# Driver.net
KiCad netlist of a schematic drawn in Altium Designer
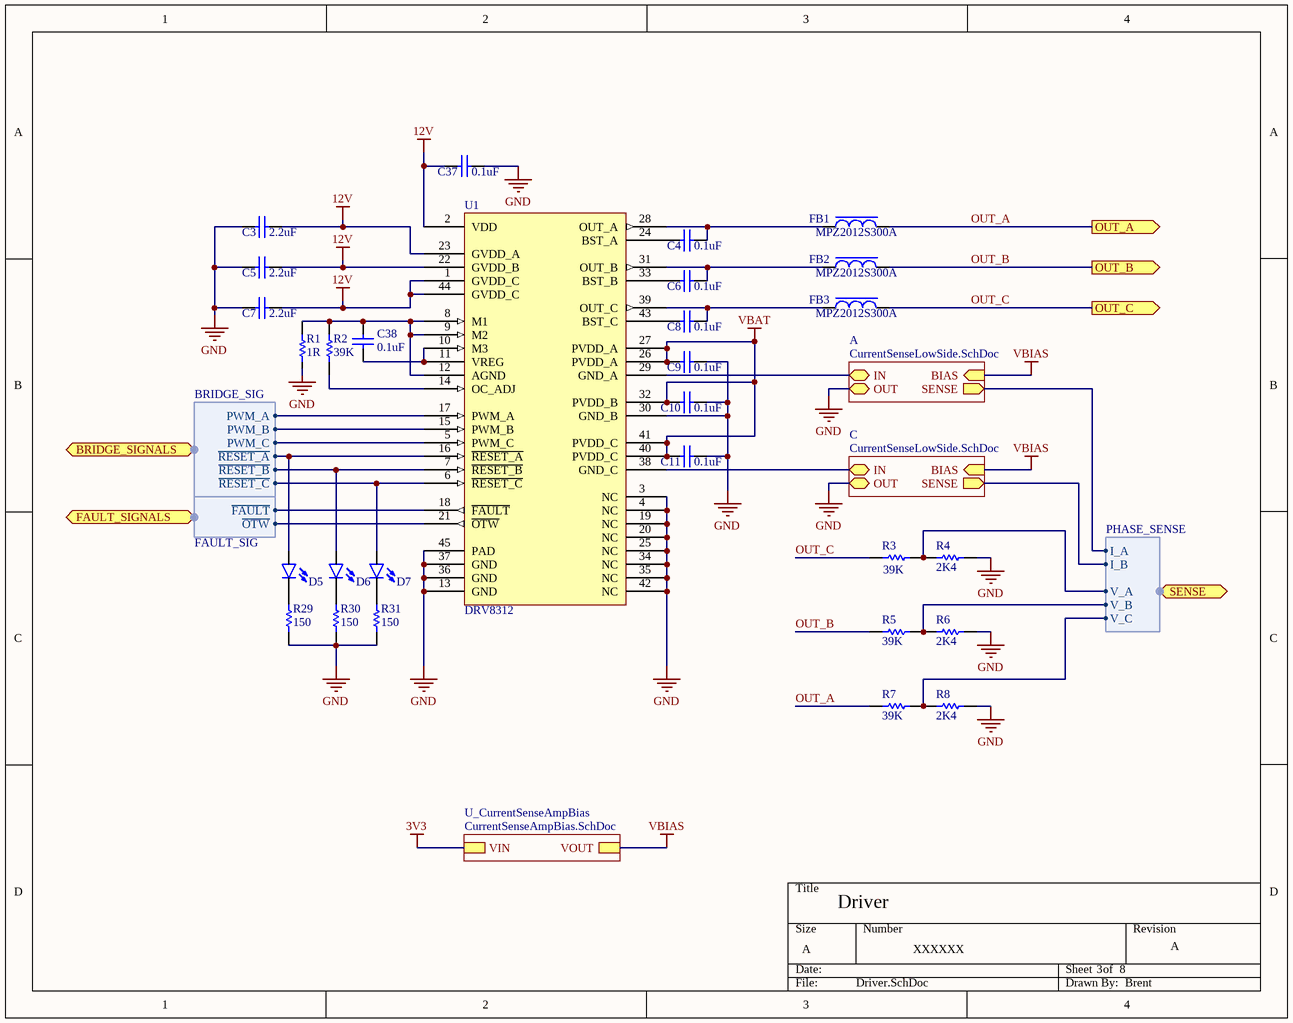
[diagram p0: Driver.SchDoc]

(export (version "E")
  (design (tool "Eeschema 10.0.6"))
  (components
    (comp (ref "C3")
      (value "2.2uF")
      (footprint "CAPC0603(1608)100_L")
      (description "CAP 2.2uF 25V ±10% 0603 (1608 Metric) Thickness 1mm SMD")
      (fields (field (name "TOLERANCE") "Â±10%"))
      (libsource (lib "Altium Content Vault") (part "CMP-1035-02767-1"))
    )
    (comp (ref "C4")
      (value "0.1uF")
      (footprint "CAPC0603(1608)100_L")
      (description "CAP 100nF 100V ±10% 0603 (1608 Metric) Thickness 1mm SMD")
      (fields (field (name "TOLERANCE") "Â±10%"))
      (libsource (lib "Altium Content Vault") (part "CAP"))
    )
    (comp (ref "C5")
      (value "2.2uF")
      (footprint "CAPC0603(1608)100_L")
      (description "CAP 2.2uF 25V ±10% 0603 (1608 Metric) Thickness 1mm SMD")
      (fields (field (name "TOLERANCE") "Â±10%"))
      (libsource (lib "Altium Content Vault") (part "CMP-1035-02767-1"))
    )
    (comp (ref "C6")
      (value "0.1uF")
      (footprint "CAPC0603(1608)100_L")
      (description "CAP 100nF 100V ±10% 0603 (1608 Metric) Thickness 1mm SMD")
      (fields (field (name "TOLERANCE") "Â±10%"))
      (libsource (lib "Altium Content Vault") (part "CAP"))
    )
    (comp (ref "C7")
      (value "2.2uF")
      (footprint "CAPC0603(1608)100_L")
      (description "CAP 2.2uF 25V ±10% 0603 (1608 Metric) Thickness 1mm SMD")
      (fields (field (name "TOLERANCE") "Â±10%"))
      (libsource (lib "Altium Content Vault") (part "CMP-1035-02767-1"))
    )
    (comp (ref "C8")
      (value "0.1uF")
      (footprint "CAPC0603(1608)100_L")
      (description "CAP 100nF 100V ±10% 0603 (1608 Metric) Thickness 1mm SMD")
      (fields (field (name "TOLERANCE") "Â±10%"))
      (libsource (lib "Altium Content Vault") (part "CAP"))
    )
    (comp (ref "C9")
      (value "0.1uF")
      (footprint "CAPC0603(1608)100_L")
      (description "CAP 100nF 100V ±10% 0603 (1608 Metric) Thickness 1mm SMD")
      (fields (field (name "TOLERANCE") "Â±10%"))
      (libsource (lib "Altium Content Vault") (part "CAP"))
    )
    (comp (ref "C10")
      (value "0.1uF")
      (footprint "CAPC0603(1608)100_L")
      (description "CAP 100nF 100V ±10% 0603 (1608 Metric) Thickness 1mm SMD")
      (fields (field (name "TOLERANCE") "Â±10%"))
      (libsource (lib "Altium Content Vault") (part "CAP"))
    )
    (comp (ref "C11")
      (value "0.1uF")
      (footprint "CAPC0603(1608)100_L")
      (description "CAP 100nF 100V ±10% 0603 (1608 Metric) Thickness 1mm SMD")
      (fields (field (name "TOLERANCE") "Â±10%"))
      (libsource (lib "Altium Content Vault") (part "CAP"))
    )
    (comp (ref "C37")
      (value "0.1uF")
      (footprint "CAPC0603(1608)100_L")
      (description "CAP 100nF 100V ±10% 0603 (1608 Metric) Thickness 1mm SMD")
      (fields (field (name "TOLERANCE") "Â±10%"))
      (libsource (lib "Altium Content Vault") (part "CAP"))
    )
    (comp (ref "C38")
      (value "0.1uF")
      (footprint "CAPC0603(1608)100_L")
      (description "CAP 100nF 100V ±10% 0603 (1608 Metric) Thickness 1mm SMD")
      (fields (field (name "TOLERANCE") "Â±10%"))
      (libsource (lib "Altium Content Vault") (part "CAP"))
    )
    (comp (ref "D5")
      (value "LED_0603_BLUE_5mA")
      (footprint "LED0603")
      (fields (field (name "PARTNUMBER") "LTST-C193TBKT-5A") (field (name "MANUFACTURER") "Lite-On Inc."))
      (libsource (lib "LEDs") (part "LED_0603_BLUE_5mA"))
    )
    (comp (ref "D6")
      (value "LED_0603_BLUE_5mA")
      (footprint "LED0603")
      (fields (field (name "PARTNUMBER") "LTST-C193TBKT-5A") (field (name "MANUFACTURER") "Lite-On Inc."))
      (libsource (lib "LEDs") (part "LED_0603_BLUE_5mA"))
    )
    (comp (ref "D7")
      (value "LED_0603_BLUE_5mA")
      (footprint "LED0603")
      (fields (field (name "PARTNUMBER") "LTST-C193TBKT-5A") (field (name "MANUFACTURER") "Lite-On Inc."))
      (libsource (lib "LEDs") (part "LED_0603_BLUE_5mA"))
    )
    (comp (ref "FB1")
      (value "MPZ2012S300A")
      (footprint "0805-Ferrite")
      (libsource (lib "Components") (part "MPZ2012S300A"))
    )
    (comp (ref "FB2")
      (value "MPZ2012S300A")
      (footprint "0805-Ferrite")
      (libsource (lib "Components") (part "MPZ2012S300A"))
    )
    (comp (ref "FB3")
      (value "MPZ2012S300A")
      (footprint "0805-Ferrite")
      (libsource (lib "Components") (part "MPZ2012S300A"))
    )
    (comp (ref "R1")
      (value "1R")
      (footprint "RESC0603(1608)_L")
      (description "1R 0.1W 5% 0603 (1608 Metric)  SMD")
      (fields (field (name "POWER") "0.1 W") (field (name "TOLERANCE") "5 %"))
      (libsource (lib "Altium Content Vault") (part "CMP-1012-00002-1"))
    )
    (comp (ref "R2")
      (value "39K")
      (footprint "RESC0603(1608)_L")
      (description "39K 0.1W 1% 0603 (1608 Metric)  SMD")
      (fields (field (name "TOLERANCE") "1 %") (field (name "POWER") "0.1 W"))
      (libsource (lib "Altium Content Vault") (part "CMP-1012-00689-1"))
    )
    (comp (ref "R3")
      (value "39K")
      (footprint "RESC0603(1608)_L")
      (description "39K 0.1W 1% 0603 (1608 Metric)  SMD")
      (fields (field (name "TOLERANCE") "1 %") (field (name "POWER") "0.1 W"))
      (libsource (lib "Altium Content Vault") (part "CMP-1012-00689-1"))
    )
    (comp (ref "R4")
      (value "2K4")
      (footprint "RESC0603(1608)_L")
      (description "2K4 0.1W 1% 0603 (1608 Metric)  SMD")
      (fields (field (name "TOLERANCE") "1 %") (field (name "POWER") "0.1 W"))
      (libsource (lib "Altium Content Vault") (part "CMP-1012-00551-1"))
    )
    (comp (ref "R5")
      (value "39K")
      (footprint "RESC0603(1608)_L")
      (description "39K 0.1W 1% 0603 (1608 Metric)  SMD")
      (fields (field (name "TOLERANCE") "1 %") (field (name "POWER") "0.1 W"))
      (libsource (lib "Altium Content Vault") (part "CMP-1012-00689-1"))
    )
    (comp (ref "R6")
      (value "2K4")
      (footprint "RESC0603(1608)_L")
      (description "2K4 0.1W 1% 0603 (1608 Metric)  SMD")
      (fields (field (name "TOLERANCE") "1 %") (field (name "POWER") "0.1 W"))
      (libsource (lib "Altium Content Vault") (part "RES"))
    )
    (comp (ref "R7")
      (value "39K")
      (footprint "RESC0603(1608)_L")
      (description "39K 0.1W 1% 0603 (1608 Metric)  SMD")
      (fields (field (name "TOLERANCE") "1 %") (field (name "POWER") "0.1 W"))
      (libsource (lib "Altium Content Vault") (part "CMP-1012-00689-1"))
    )
    (comp (ref "R8")
      (value "2K4")
      (footprint "RESC0603(1608)_L")
      (description "2K4 0.1W 1% 0603 (1608 Metric)  SMD")
      (fields (field (name "TOLERANCE") "1 %") (field (name "POWER") "0.1 W"))
      (libsource (lib "Altium Content Vault") (part "CMP-1012-00551-1"))
    )
    (comp (ref "R29")
      (value "150")
      (footprint "RESC0603(1608)_L")
      (description "150R 0.1W 1% 0603 (1608 Metric)  SMD")
      (fields (field (name "TOLERANCE") "1 %") (field (name "POWER") "0.1 W"))
      (libsource (lib "Altium Content Vault") (part "CMP-1012-00415-1"))
    )
    (comp (ref "R30")
      (value "150")
      (footprint "RESC0603(1608)_L")
      (description "150R 0.1W 1% 0603 (1608 Metric)  SMD")
      (fields (field (name "TOLERANCE") "1 %") (field (name "POWER") "0.1 W"))
      (libsource (lib "Altium Content Vault") (part "CMP-1012-00415-1"))
    )
    (comp (ref "R31")
      (value "150")
      (footprint "RESC0603(1608)_L")
      (description "150R 0.1W 1% 0603 (1608 Metric)  SMD")
      (fields (field (name "TOLERANCE") "1 %") (field (name "POWER") "0.1 W"))
      (libsource (lib "Altium Content Vault") (part "CMP-1012-00415-1"))
    )
    (comp (ref "U1")
      (value "DRV8312")
      (footprint "HTSSOP-44E")
      (libsource (lib "Components") (part "DRV8312"))
    )
  )
  (nets
    (net (code "5") (name "/IN") (class "Default")
      (node (ref "U1") (pin "38") (pinfunction "GND_C_38") (pintype "power_in"))
    )
    (net (code "6") (name "/IN_1") (class "Default")
      (node (ref "U1") (pin "29") (pinfunction "GND_A_29") (pintype "power_in"))
    )
    (net (code "7") (name "/OUT_A") (class "Default")
      (node (ref "FB1") (pin "2") (pinfunction "2_2") (pintype "passive"))
      (node (ref "R7") (pin "2") (pinfunction "2_2") (pintype "passive"))
    )
    (net (code "8") (name "/OUT_B") (class "Default")
      (node (ref "FB2") (pin "2") (pinfunction "2_2") (pintype "passive"))
      (node (ref "R5") (pin "2") (pinfunction "2_2") (pintype "passive"))
    )
    (net (code "9") (name "/OUT_C") (class "Default")
      (node (ref "FB3") (pin "2") (pinfunction "2_2") (pintype "passive"))
      (node (ref "R3") (pin "2") (pinfunction "2_2") (pintype "passive"))
    )
    (net (code "15") (name "12V") (class "Default")
      (node (ref "C3") (pin "1") (pinfunction "1_1") (pintype "passive"))
      (node (ref "C37") (pin "1") (pinfunction "1_1") (pintype "passive"))
      (node (ref "C5") (pin "1") (pinfunction "1_1") (pintype "passive"))
      (node (ref "C7") (pin "1") (pinfunction "1_1") (pintype "passive"))
      (node (ref "U1") (pin "1") (pinfunction "GVDD_C_1") (pintype "power_in"))
      (node (ref "U1") (pin "2") (pinfunction "VDD_2") (pintype "power_in"))
      (node (ref "U1") (pin "22") (pinfunction "GVDD_B_22") (pintype "power_in"))
      (node (ref "U1") (pin "23") (pinfunction "GVDD_A_23") (pintype "power_in"))
      (node (ref "U1") (pin "44") (pinfunction "GVDD_C_44") (pintype "power_in"))
    )
    (net (code "16") (name "GND") (class "Default")
      (node (ref "C10") (pin "2") (pinfunction "2_2") (pintype "passive"))
      (node (ref "C11") (pin "2") (pinfunction "2_2") (pintype "passive"))
      (node (ref "C3") (pin "2") (pinfunction "2_2") (pintype "passive"))
      (node (ref "C37") (pin "2") (pinfunction "2_2") (pintype "passive"))
      (node (ref "C5") (pin "2") (pinfunction "2_2") (pintype "passive"))
      (node (ref "C7") (pin "2") (pinfunction "2_2") (pintype "passive"))
      (node (ref "C9") (pin "2") (pinfunction "2_2") (pintype "passive"))
      (node (ref "R1") (pin "2") (pinfunction "2_2") (pintype "passive"))
      (node (ref "R29") (pin "1") (pinfunction "1_1") (pintype "passive"))
      (node (ref "R30") (pin "1") (pinfunction "1_1") (pintype "passive"))
      (node (ref "R31") (pin "1") (pinfunction "1_1") (pintype "passive"))
      (node (ref "R4") (pin "1") (pinfunction "1_1") (pintype "passive"))
      (node (ref "R6") (pin "1") (pinfunction "1_1") (pintype "passive"))
      (node (ref "R8") (pin "1") (pinfunction "1_1") (pintype "passive"))
      (node (ref "U1") (pin "13") (pinfunction "GND_13") (pintype "power_in"))
      (node (ref "U1") (pin "19") (pinfunction "NC_19") (pintype "passive"))
      (node (ref "U1") (pin "20") (pinfunction "NC_20") (pintype "passive"))
      (node (ref "U1") (pin "25") (pinfunction "NC_25") (pintype "passive"))
      (node (ref "U1") (pin "3") (pinfunction "NC_3") (pintype "passive"))
      (node (ref "U1") (pin "30") (pinfunction "GND_B_30") (pintype "power_in"))
      (node (ref "U1") (pin "34") (pinfunction "NC_34") (pintype "passive"))
      (node (ref "U1") (pin "35") (pinfunction "NC_35") (pintype "passive"))
      (node (ref "U1") (pin "36") (pinfunction "GND_36") (pintype "power_in"))
      (node (ref "U1") (pin "37") (pinfunction "GND_37") (pintype "power_in"))
      (node (ref "U1") (pin "4") (pinfunction "NC_4") (pintype "passive"))
      (node (ref "U1") (pin "42") (pinfunction "NC_42") (pintype "passive"))
      (node (ref "U1") (pin "45") (pinfunction "PAD_45") (pintype "power_in"))
    )
    (net (code "17") (name "Net-(D5-PadC)") (class "Default")
      (node (ref "D5") (pin "C") (pinfunction "C_C") (pintype "passive"))
      (node (ref "R29") (pin "2") (pinfunction "2_2") (pintype "passive"))
    )
    (net (code "18") (name "Net-(D6-PadC)") (class "Default")
      (node (ref "D6") (pin "C") (pinfunction "C_C") (pintype "passive"))
      (node (ref "R30") (pin "2") (pinfunction "2_2") (pintype "passive"))
    )
    (net (code "19") (name "Net-(D7-PadC)") (class "Default")
      (node (ref "D7") (pin "C") (pinfunction "C_C") (pintype "passive"))
      (node (ref "R31") (pin "2") (pinfunction "2_2") (pintype "passive"))
    )
    (net (code "20") (name "Net-(R3-Pad1)") (class "Default")
      (node (ref "R3") (pin "1") (pinfunction "1_1") (pintype "passive"))
      (node (ref "R4") (pin "2") (pinfunction "2_2") (pintype "passive"))
    )
    (net (code "21") (name "Net-(R5-Pad1)") (class "Default")
      (node (ref "R5") (pin "1") (pinfunction "1_1") (pintype "passive"))
      (node (ref "R6") (pin "2") (pinfunction "2_2") (pintype "passive"))
    )
    (net (code "22") (name "Net-(R7-Pad1)") (class "Default")
      (node (ref "R7") (pin "1") (pinfunction "1_1") (pintype "passive"))
      (node (ref "R8") (pin "2") (pinfunction "2_2") (pintype "passive"))
    )
    (net (code "23") (name "Net-(U1-AGND)") (class "Default")
      (node (ref "C38") (pin "2") (pinfunction "2_2") (pintype "passive"))
      (node (ref "R1") (pin "1") (pinfunction "1_1") (pintype "passive"))
      (node (ref "R2") (pin "2") (pinfunction "2_2") (pintype "passive"))
      (node (ref "U1") (pin "12") (pinfunction "AGND_12") (pintype "power_in"))
      (node (ref "U1") (pin "8") (pinfunction "M1_8") (pintype "input"))
      (node (ref "U1") (pin "9") (pinfunction "M2_9") (pintype "input"))
    )
    (net (code "24") (name "Net-(U1-BST_A)") (class "Default")
      (node (ref "C4") (pin "1") (pinfunction "1_1") (pintype "passive"))
      (node (ref "U1") (pin "24") (pinfunction "BST_A_24") (pintype "power_in"))
    )
    (net (code "25") (name "Net-(U1-BST_B)") (class "Default")
      (node (ref "C6") (pin "1") (pinfunction "1_1") (pintype "passive"))
      (node (ref "U1") (pin "33") (pinfunction "BST_B_33") (pintype "power_in"))
    )
    (net (code "26") (name "Net-(U1-BST_C)") (class "Default")
      (node (ref "C8") (pin "1") (pinfunction "1_1") (pintype "passive"))
      (node (ref "U1") (pin "43") (pinfunction "BST_C_43") (pintype "power_in"))
    )
    (net (code "27") (name "Net-(U1-M3)") (class "Default")
      (node (ref "C38") (pin "1") (pinfunction "1_1") (pintype "passive"))
      (node (ref "U1") (pin "10") (pinfunction "M3_10") (pintype "input"))
      (node (ref "U1") (pin "11") (pinfunction "VREG_11") (pintype "power_in"))
    )
    (net (code "28") (name "Net-(U1-OC_ADJ)") (class "Default")
      (node (ref "R2") (pin "1") (pinfunction "1_1") (pintype "passive"))
      (node (ref "U1") (pin "14") (pinfunction "OC_ADJ_14") (pintype "input"))
    )
    (net (code "29") (name "Net-(U1-OUT_A)") (class "Default")
      (node (ref "C4") (pin "2") (pinfunction "2_2") (pintype "passive"))
      (node (ref "FB1") (pin "1") (pinfunction "1_1") (pintype "passive"))
      (node (ref "U1") (pin "28") (pinfunction "OUT_A_28") (pintype "output"))
    )
    (net (code "30") (name "Net-(U1-OUT_B)") (class "Default")
      (node (ref "C6") (pin "2") (pinfunction "2_2") (pintype "passive"))
      (node (ref "FB2") (pin "1") (pinfunction "1_1") (pintype "passive"))
      (node (ref "U1") (pin "31") (pinfunction "OUT_B_31") (pintype "output"))
    )
    (net (code "31") (name "Net-(U1-OUT_C)") (class "Default")
      (node (ref "C8") (pin "2") (pinfunction "2_2") (pintype "passive"))
      (node (ref "FB3") (pin "1") (pinfunction "1_1") (pintype "passive"))
      (node (ref "U1") (pin "39") (pinfunction "OUT_C_39") (pintype "output"))
    )
    (net (code "32") (name "Net-(U1-~{RESET_A})") (class "Default")
      (node (ref "D5") (pin "A") (pinfunction "A_A") (pintype "passive"))
      (node (ref "U1") (pin "16") (pinfunction "~{RESET_A}_16") (pintype "input"))
    )
    (net (code "33") (name "Net-(U1-~{RESET_B})") (class "Default")
      (node (ref "D6") (pin "A") (pinfunction "A_A") (pintype "passive"))
      (node (ref "U1") (pin "7") (pinfunction "~{RESET_B}_7") (pintype "input"))
    )
    (net (code "34") (name "Net-(U1-~{RESET_C})") (class "Default")
      (node (ref "D7") (pin "A") (pinfunction "A_A") (pintype "passive"))
      (node (ref "U1") (pin "6") (pinfunction "~{RESET_C}_6") (pintype "input"))
    )
    (net (code "35") (name "VBAT") (class "Default")
      (node (ref "C10") (pin "1") (pinfunction "1_1") (pintype "passive"))
      (node (ref "C11") (pin "1") (pinfunction "1_1") (pintype "passive"))
      (node (ref "C9") (pin "1") (pinfunction "1_1") (pintype "passive"))
      (node (ref "U1") (pin "26") (pinfunction "PVDD_A_26") (pintype "power_in"))
      (node (ref "U1") (pin "27") (pinfunction "PVDD_A_27") (pintype "power_in"))
      (node (ref "U1") (pin "32") (pinfunction "PVDD_B_32") (pintype "power_in"))
      (node (ref "U1") (pin "40") (pinfunction "PVDD_C_40") (pintype "power_in"))
      (node (ref "U1") (pin "41") (pinfunction "PVDD_C_41") (pintype "power_in"))
    )
    (net (code "37") (name "unconnected-(U1-PWM_A-Pad17)") (class "Default")
      (node (ref "U1") (pin "17") (pinfunction "PWM_A_17") (pintype "input"))
    )
    (net (code "38") (name "unconnected-(U1-PWM_B-Pad15)") (class "Default")
      (node (ref "U1") (pin "15") (pinfunction "PWM_B_15") (pintype "input"))
    )
    (net (code "39") (name "unconnected-(U1-PWM_C-Pad5)") (class "Default")
      (node (ref "U1") (pin "5") (pinfunction "PWM_C_5") (pintype "input"))
    )
    (net (code "40") (name "unconnected-(U1-~{FAULT}-Pad18)") (class "Default")
      (node (ref "U1") (pin "18") (pinfunction "~{FAULT}_18") (pintype "output"))
    )
    (net (code "41") (name "unconnected-(U1-~{OTW}-Pad21)") (class "Default")
      (node (ref "U1") (pin "21") (pinfunction "~{OTW}_21") (pintype "output"))
    )
  )
)
